# soundfield_board_40720_12_5mm.net
KiCad netlist of a schematic drawn in EAGLE
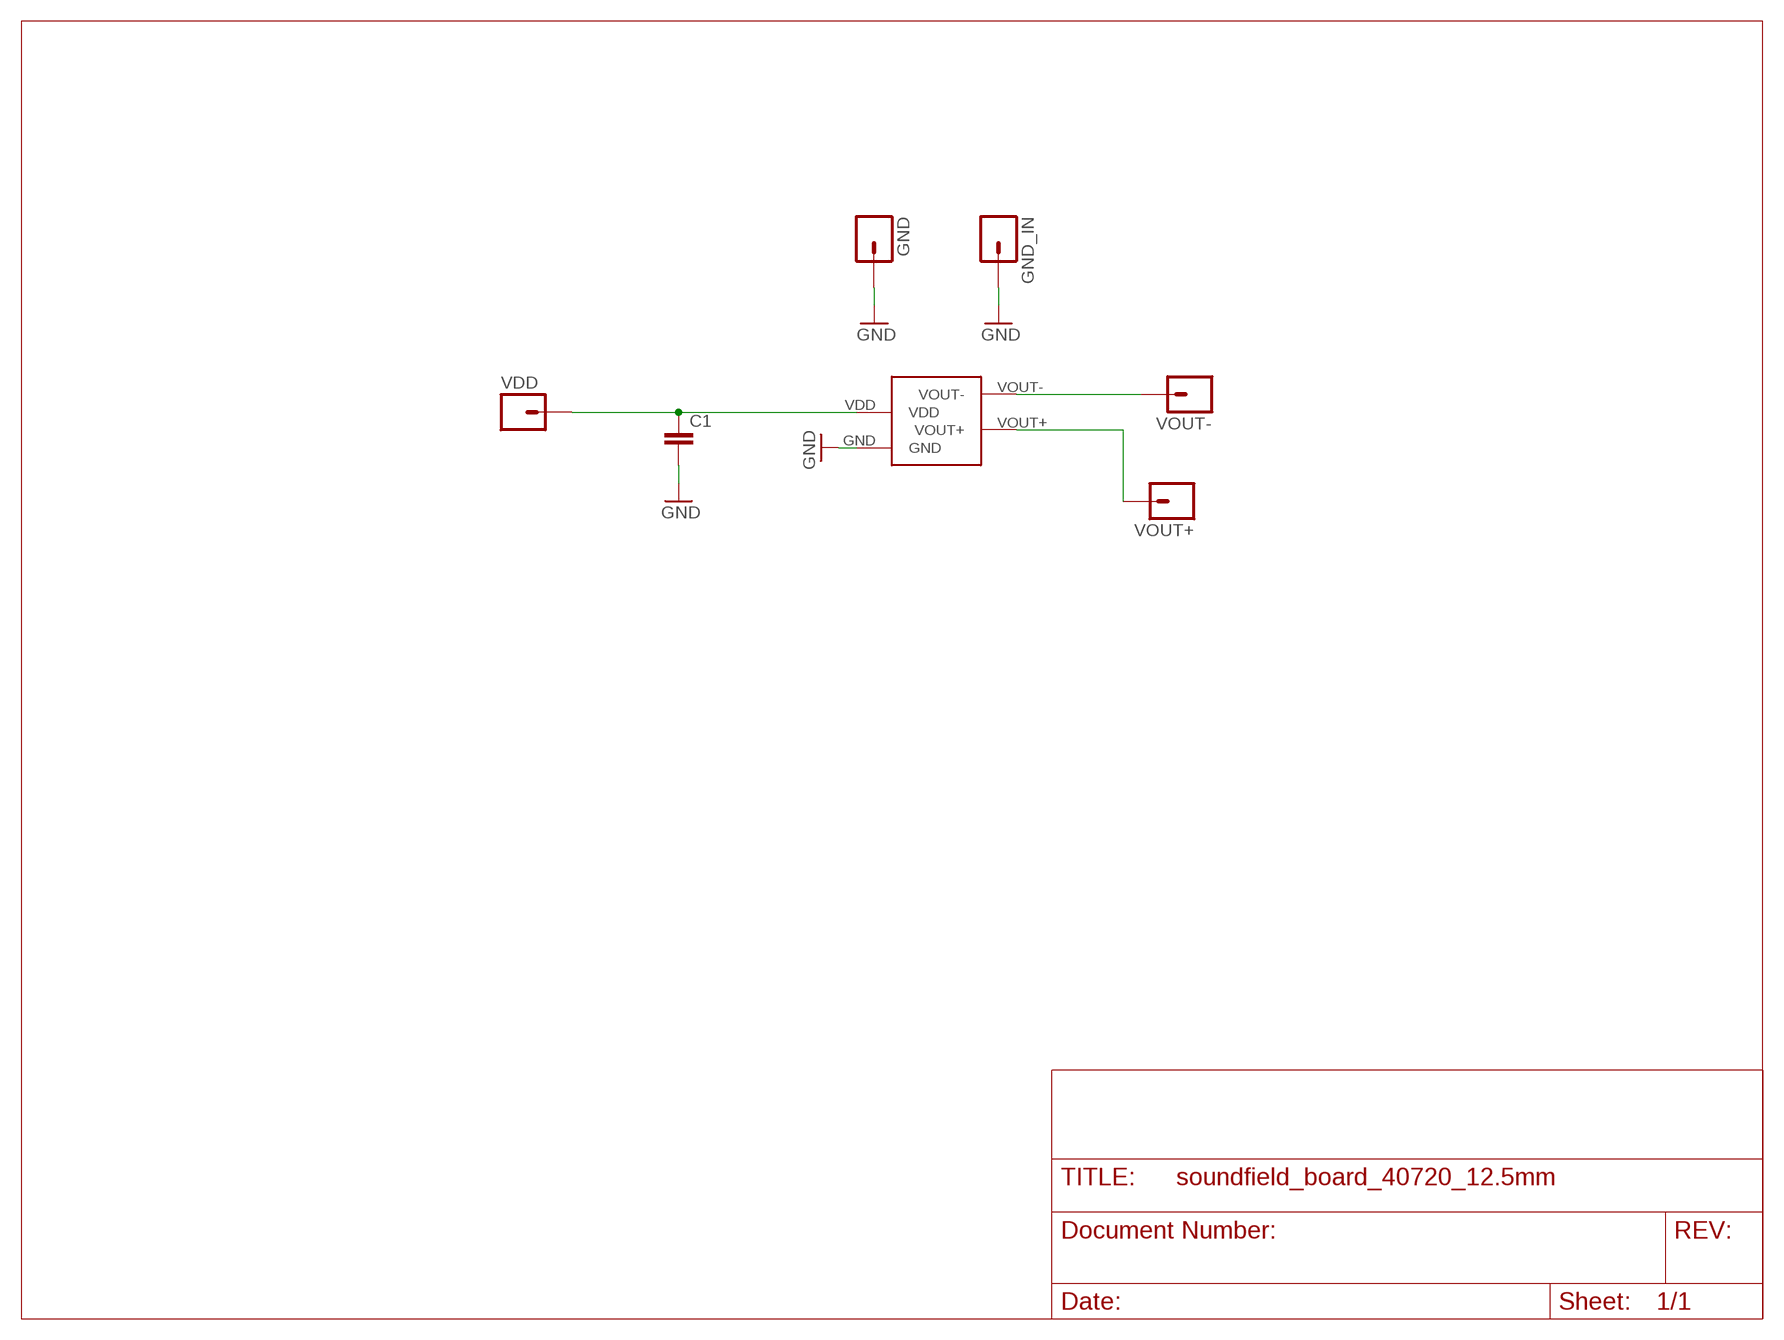
[diagram p0: schematic, sheet 1]

(export (version "E")
  (design (tool "Eeschema 10.0.6"))
  (components
    (comp (ref "C1")
      (value "0.1UF-16V(+-10%)(0402)")
      (footprint "eagle-import:0402-CAP")
      (libsource (lib "eagle-import") (part "0.1UF-16V(+-10%)(0402)"))
    )
    (comp (ref "GND")
      (value "M01PTH_NO_SILK_YES_STOP")
      (footprint "eagle-import:1X01_NO_SILK")
      (libsource (lib "eagle-import") (part "CM-SparkFun-Connectors-large_hole_M01PTH_NO_SILK_YES_STOP"))
    )
    (comp (ref "GND_IN")
      (value "M01PTH")
      (footprint "eagle-import:1X01")
      (libsource (lib "eagle-import") (part "CM-SparkFun-Connectors-2_M01PTH"))
    )
    (comp (ref "U$1")
      (value "MEMS_ICS_40720")
      (footprint "eagle-import: MEMS_ICS_40720")
      (libsource (lib "eagle-import") (part " MEMS_ICS_40720"))
    )
    (comp (ref "VDD")
      (value "M01PTH")
      (footprint "eagle-import:1X01")
      (libsource (lib "eagle-import") (part "M01PTH"))
    )
    (comp (ref "VOUT+")
      (value "M01PTH")
      (footprint "eagle-import:1X01")
      (libsource (lib "eagle-import") (part "M01PTH"))
    )
    (comp (ref "VOUT-")
      (value "M01PTH")
      (footprint "eagle-import:1X01")
      (libsource (lib "eagle-import") (part "M01PTH"))
    )
  )
  (nets
    (net (code "1") (name "GND") (class "Default")
      (node (ref "C1") (pin "2") (pinfunction "2_2") (pintype "passive"))
      (node (ref "GND") (pin "1") (pinfunction "1_1") (pintype "passive"))
      (node (ref "GND_IN") (pin "1") (pinfunction "1_1") (pintype "passive"))
      (node (ref "U$1") (pin "GND") (pinfunction "GND_GND") (pintype "input"))
    )
    (net (code "2") (name "Net-(C1-Pad1)") (class "Default")
      (node (ref "C1") (pin "1") (pinfunction "1_1") (pintype "passive"))
      (node (ref "U$1") (pin "VDD") (pinfunction "VDD_VDD") (pintype "power_in"))
      (node (ref "VDD") (pin "1") (pinfunction "1_1") (pintype "passive"))
    )
    (net (code "3") (name "Net-(U$1-PadVOUT+)") (class "Default")
      (node (ref "U$1") (pin "VOUT+") (pinfunction "VOUT+_VOUT+") (pintype "input"))
      (node (ref "VOUT+") (pin "1") (pinfunction "1_1") (pintype "passive"))
    )
    (net (code "4") (name "Net-(U$1-PadVOUT-)") (class "Default")
      (node (ref "U$1") (pin "VOUT-") (pinfunction "VOUT-_VOUT-") (pintype "input"))
      (node (ref "VOUT-") (pin "1") (pinfunction "1_1") (pintype "passive"))
    )
  )
)
